# Elkapod_power_supply_controller_module.net
KiCad netlist of a schematic drawn in Altium Designer
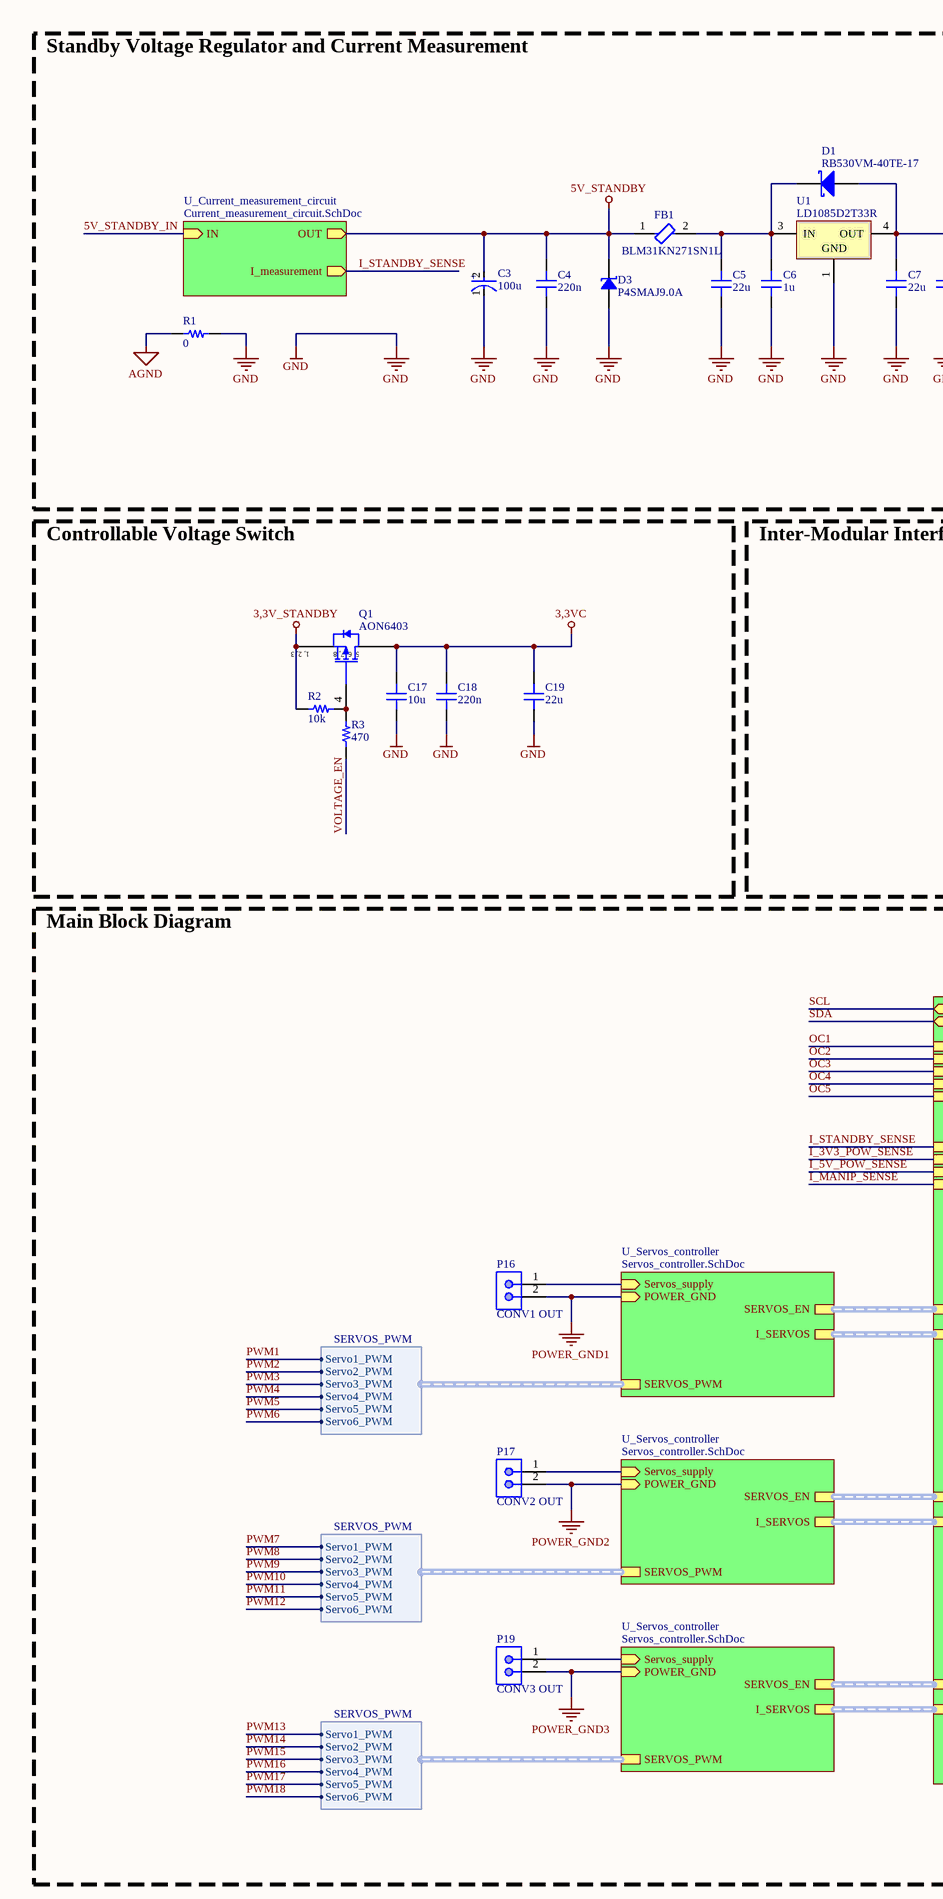
[diagram p0: Elkapod_power_supply_controller_module.SchDoc, left]
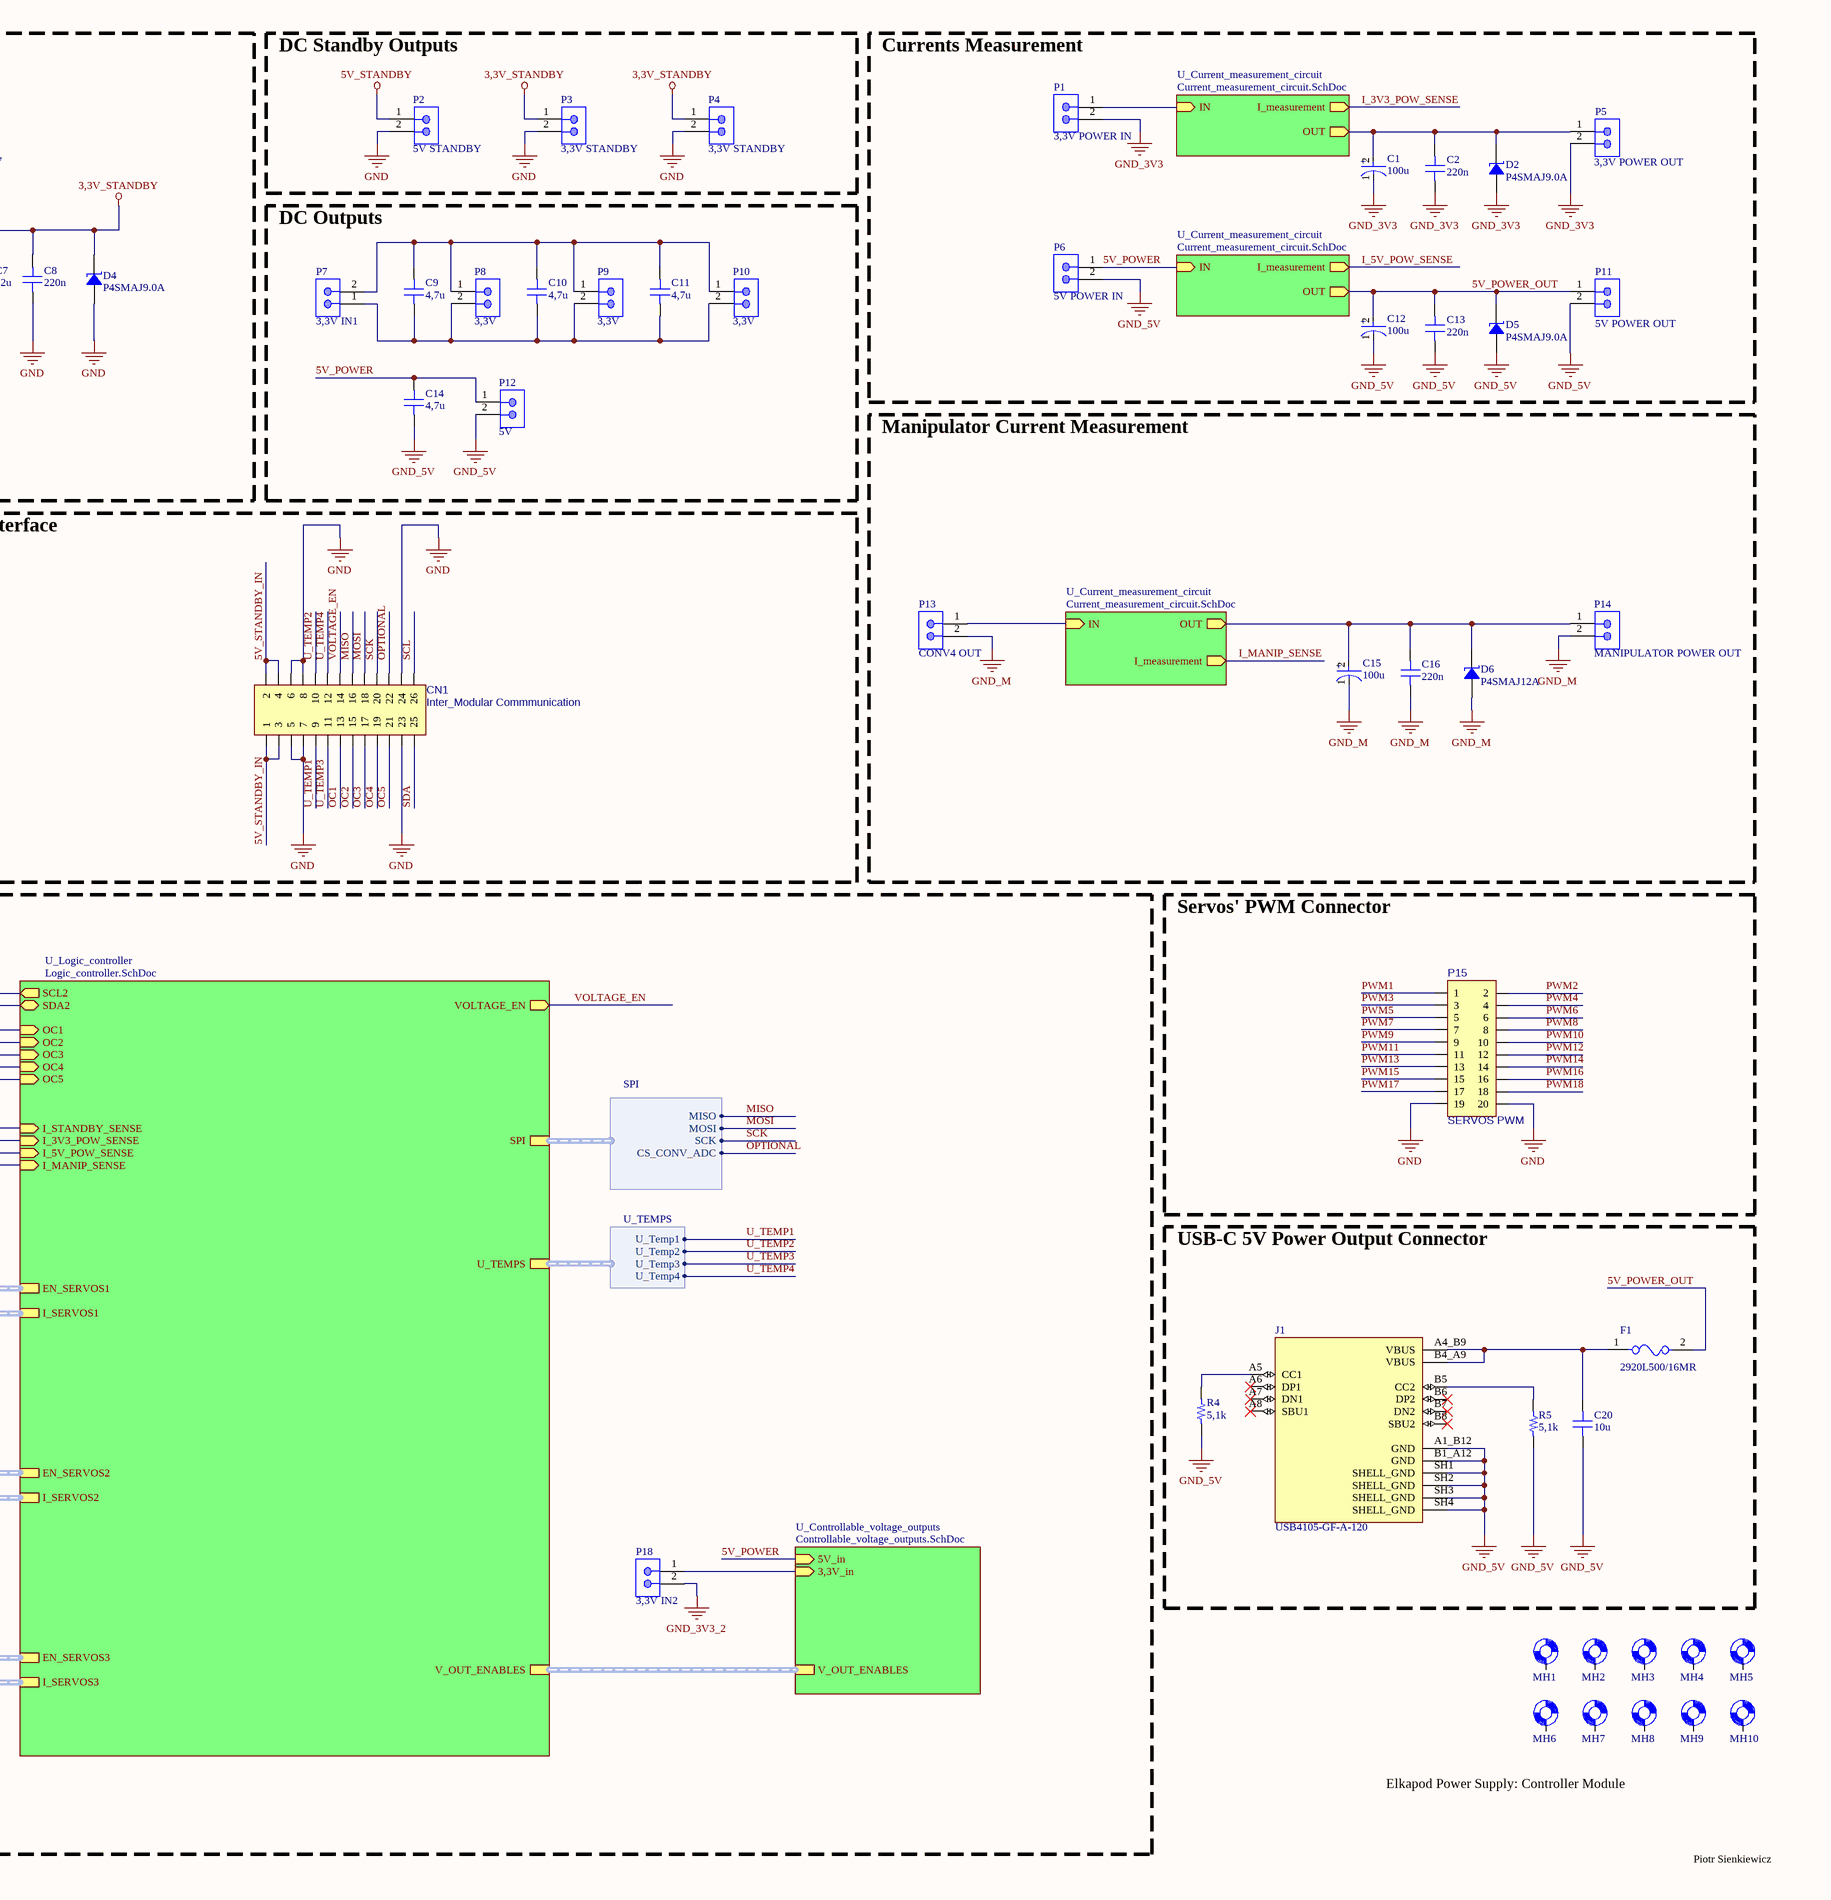
[diagram p1: Elkapod_power_supply_controller_module.SchDoc, right]

(export (version "E")
  (design (tool "Eeschema 10.0.6"))
  (components
    (comp (ref "C1")
      (value "100u")
      (footprint "FP-FKE-MFG")
      (description "CAP ALUM 100UF 20% 25V SMD")
      (fields (field (name "TOLERANCE") "20%") (field (name "VOLTAGE") "25V"))
      (libsource (lib "Altium Content Vault") (part "203bc49f2ac43e59fd269a8c329ed05"))
    )
    (comp (ref "C2")
      (value "220n")
      (footprint "CAP 0603_1608")
      (description "CAP CER 220nF 25V X5R 0603")
      (fields (field (name "PART NUMBER") "C0603C272F3GAC7867") (field (name "MANUFACTURER") "KEMET"))
      (libsource (lib "Celestial Altium Library - altium_library") (part "Capacitor"))
    )
    (comp (ref "C3")
      (value "100u")
      (footprint "FP-FKE-MFG")
      (description "CAP ALUM 100UF 20% 25V SMD")
      (fields (field (name "TOLERANCE") "20%") (field (name "VOLTAGE") "25V"))
      (libsource (lib "Altium Content Vault") (part "203bc49f2ac43e59fd269a8c329ed05"))
    )
    (comp (ref "C4")
      (value "220n")
      (footprint "CAP 0603_1608")
      (description "CAP CER 220nF 25V X5R 0603")
      (fields (field (name "PART NUMBER") "C0603C272F3GAC7867") (field (name "MANUFACTURER") "KEMET"))
      (libsource (lib "Celestial Altium Library - altium_library") (part "Capacitor"))
    )
    (comp (ref "C5")
      (value "22u")
      (footprint "CAP 0805_2012")
      (description "CAP CER 22UF 25V X7R 0805")
      (fields
        (field (name "PART NUMBER") "VJ0805Y684KXQTW1BC")
        (field (name "MANUFACTURER") "Vishay Vitramon")
      )
      (libsource (lib "Celestial Altium Library - altium_library") (part "Capacitor"))
    )
    (comp (ref "C6")
      (value "1u")
      (footprint "CAP 0603_1608")
      (description "CAP CER 1uF 16V X5R 0603")
      (fields (field (name "PART NUMBER") "C0603C272F3GAC7867") (field (name "MANUFACTURER") "KEMET"))
      (libsource (lib "Celestial Altium Library - altium_library") (part "Capacitor"))
    )
    (comp (ref "C7")
      (value "22u")
      (footprint "CAP 0805_2012")
      (description "CAP CER 22UF 25V X7R 0805")
      (fields
        (field (name "PART NUMBER") "VJ0805Y684KXQTW1BC")
        (field (name "MANUFACTURER") "Vishay Vitramon")
      )
      (libsource (lib "Celestial Altium Library - altium_library") (part "Capacitor"))
    )
    (comp (ref "C8")
      (value "220n")
      (footprint "CAP 0603_1608")
      (description "CAP CER 220nF 25V X5R 0603")
      (fields (field (name "PART NUMBER") "C0603C272F3GAC7867") (field (name "MANUFACTURER") "KEMET"))
      (libsource (lib "Celestial Altium Library - altium_library") (part "Capacitor"))
    )
    (comp (ref "C9")
      (value "4,7u")
      (footprint "CAP 0603_1608")
      (description "CAP CER 4,7uF 25V X5R 0603")
      (fields (field (name "PART NUMBER") "C0603C272F3GAC7867") (field (name "MANUFACTURER") "KEMET"))
      (libsource (lib "Celestial Altium Library - altium_library") (part "Capacitor"))
    )
    (comp (ref "C10")
      (value "4,7u")
      (footprint "CAP 0603_1608")
      (description "CAP CER 4,7uF 25V X5R 0603")
      (fields (field (name "PART NUMBER") "C0603C272F3GAC7867") (field (name "MANUFACTURER") "KEMET"))
      (libsource (lib "Celestial Altium Library - altium_library") (part "Capacitor"))
    )
    (comp (ref "C11")
      (value "4,7u")
      (footprint "CAP 0603_1608")
      (description "CAP CER 4,7uF 25V X5R 0603")
      (fields (field (name "PART NUMBER") "C0603C272F3GAC7867") (field (name "MANUFACTURER") "KEMET"))
      (libsource (lib "Celestial Altium Library - altium_library") (part "Capacitor"))
    )
    (comp (ref "C12")
      (value "100u")
      (footprint "FP-FKE-MFG")
      (description "CAP ALUM 100UF 20% 25V SMD")
      (fields (field (name "TOLERANCE") "20%") (field (name "VOLTAGE") "25V"))
      (libsource (lib "Altium Content Vault") (part "203bc49f2ac43e59fd269a8c329ed05"))
    )
    (comp (ref "C13")
      (value "220n")
      (footprint "CAP 0603_1608")
      (description "CAP CER 220nF 25V X5R 0603")
      (fields (field (name "PART NUMBER") "C0603C272F3GAC7867") (field (name "MANUFACTURER") "KEMET"))
      (libsource (lib "Celestial Altium Library - altium_library") (part "Capacitor"))
    )
    (comp (ref "C14")
      (value "4,7u")
      (footprint "CAP 0603_1608")
      (description "CAP CER 4,7uF 25V X5R 0603")
      (fields (field (name "PART NUMBER") "C0603C272F3GAC7867") (field (name "MANUFACTURER") "KEMET"))
      (libsource (lib "Celestial Altium Library - altium_library") (part "Capacitor"))
    )
    (comp (ref "C15")
      (value "100u")
      (footprint "FP-FKE-MFG")
      (description "CAP ALUM 100UF 20% 25V SMD")
      (fields (field (name "TOLERANCE") "20%") (field (name "VOLTAGE") "25V"))
      (libsource (lib "Altium Content Vault") (part "203bc49f2ac43e59fd269a8c329ed05"))
    )
    (comp (ref "C16")
      (value "220n")
      (footprint "CAP 0603_1608")
      (description "CAP CER 220nF 25V X5R 0603")
      (fields (field (name "PART NUMBER") "C0603C272F3GAC7867") (field (name "MANUFACTURER") "KEMET"))
      (libsource (lib "Celestial Altium Library - altium_library") (part "Capacitor"))
    )
    (comp (ref "C17")
      (value "10u")
      (footprint "CAP 0603_1608")
      (description "CAP CER 10uF 35V X5R 0603")
      (fields (field (name "PART NUMBER") "C0603C272F3GAC7867") (field (name "MANUFACTURER") "KEMET"))
      (libsource (lib "Celestial Altium Library - altium_library") (part "Capacitor"))
    )
    (comp (ref "C18")
      (value "220n")
      (footprint "CAP 0603_1608")
      (description "CAP CER 220nF 25V X5R 0603")
      (fields (field (name "PART NUMBER") "C0603C272F3GAC7867") (field (name "MANUFACTURER") "KEMET"))
      (libsource (lib "Celestial Altium Library - altium_library") (part "Capacitor"))
    )
    (comp (ref "C19")
      (value "22u")
      (footprint "CAP 0805_2012")
      (description "CAP CER 22UF 25V X7R 0805")
      (fields
        (field (name "PART NUMBER") "VJ0805Y684KXQTW1BC")
        (field (name "MANUFACTURER") "Vishay Vitramon")
      )
      (libsource (lib "Celestial Altium Library - altium_library") (part "Capacitor"))
    )
    (comp (ref "C20")
      (value "10u")
      (footprint "CAP 0603_1608")
      (description "CAP CER 10uF 35V X5R 0603")
      (fields (field (name "PART NUMBER") "C0603C272F3GAC7867") (field (name "MANUFACTURER") "KEMET"))
      (libsource (lib "Celestial Altium Library - altium_library") (part "Capacitor"))
    )
    (comp (ref "CN1")
      (value "Inter_Modular Commmunication")
      (footprint "GP_13x2")
      (libsource (lib "goldpin_male") (part "CN_13x2"))
    )
    (comp (ref "D1")
      (value "RB530VM-40TE-17")
      (footprint "SOD-323")
      (description "Schottky diode; 0,1A; 40V")
      (fields (field (name "PUBLISHER") "Altium Limited"))
      (libsource (lib "Infineon Discrete Diode") (part "BAS140W"))
    )
    (comp (ref "D2")
      (value "P4SMAJ9.0A")
      (footprint "DO214AC SMA")
      (description "TVS DIODE 9VDC DO214AC")
      (libsource (lib "Celestial Altium Library - altium_library") (part "DIODE TVS UNI"))
    )
    (comp (ref "D3")
      (value "P4SMAJ9.0A")
      (footprint "DO214AC SMA")
      (description "TVS DIODE 9VDC DO214AC")
      (libsource (lib "Celestial Altium Library - altium_library") (part "DIODE TVS UNI"))
    )
    (comp (ref "D4")
      (value "P4SMAJ9.0A")
      (footprint "DO214AC SMA")
      (description "TVS DIODE 9VDC DO214AC")
      (libsource (lib "Celestial Altium Library - altium_library") (part "DIODE TVS UNI"))
    )
    (comp (ref "D5")
      (value "P4SMAJ9.0A")
      (footprint "DO214AC SMA")
      (description "TVS DIODE 9VDC DO214AC")
      (libsource (lib "Celestial Altium Library - altium_library") (part "DIODE TVS UNI"))
    )
    (comp (ref "D6")
      (value "P4SMAJ12A")
      (footprint "DO214AC SMA")
      (description "TVS DIODE 12VDC DO214AC")
      (fields (field (name "PART NUMBER") "P4SMAJ9.0A"))
      (libsource (lib "Celestial Altium Library - altium_library") (part "DIODE TVS UNI"))
    )
    (comp (ref "F1")
      (value "2920L500/16MR")
      (footprint "FP-2920L-MFG")
      (description "PTC RESET FUSE 16V 5A 2920")
      (fields
        (field (name "MANUFACTURER") "Littelfuse")
        (field (name "OCTOPART") "https://octopart.com/2920l500%2F16mr-littelfuse-28867177")
      )
      (libsource (lib "Altium Content Vault") (part "5bcf9b9f640e542cf0359d10258e979"))
    )
    (comp (ref "FB1")
      (value "BLM31KN271SN1L")
      (footprint "FP-BLM31-0_2-t1_6-d3_3-MFG")
      (description "Chip Ferrite Bead, 1206, 270Ω @ 100MHz, 0.016Ω, 25%, 4.5A")
      (libsource (lib "Altium Content Vault") (part "5f30dd21d616792df468990f7003faa"))
    )
    (comp (ref "J1")
      (value "USB4105-GF-A-120")
      (footprint "USB4105-GF-A-120")
      (description "USB C socket; SMT; PIN: 16; top board mount; 5A")
      (libsource (lib "My_sockets") (part "USB4105-GF-A-120"))
    )
    (comp (ref "MH1")
      (value "M3 Mounting Hole")
      (footprint "M3_MOUNTING_HOLE")
      (libsource (lib "My_mounting_components") (part "M3 Mounting Hole"))
    )
    (comp (ref "MH2")
      (value "M3 Mounting Hole")
      (footprint "M3_MOUNTING_HOLE")
      (libsource (lib "My_mounting_components") (part "M3 Mounting Hole"))
    )
    (comp (ref "MH3")
      (value "M3 Mounting Hole")
      (footprint "M3_MOUNTING_HOLE")
      (libsource (lib "My_mounting_components") (part "M3 Mounting Hole"))
    )
    (comp (ref "MH4")
      (value "M3 Mounting Hole")
      (footprint "M3_MOUNTING_HOLE")
      (libsource (lib "My_mounting_components") (part "M3 Mounting Hole"))
    )
    (comp (ref "MH5")
      (value "M3 Mounting Hole")
      (footprint "M3_MOUNTING_HOLE")
      (libsource (lib "My_mounting_components") (part "M3 Mounting Hole"))
    )
    (comp (ref "MH6")
      (value "M3 Mounting Hole")
      (footprint "M3_MOUNTING_HOLE")
      (libsource (lib "My_mounting_components") (part "M3 Mounting Hole"))
    )
    (comp (ref "MH7")
      (value "M3 Mounting Hole")
      (footprint "M3_MOUNTING_HOLE")
      (libsource (lib "My_mounting_components") (part "M3 Mounting Hole"))
    )
    (comp (ref "MH8")
      (value "M3 Mounting Hole")
      (footprint "M3_MOUNTING_HOLE")
      (libsource (lib "My_mounting_components") (part "M3 Mounting Hole"))
    )
    (comp (ref "MH9")
      (value "M3 Mounting Hole")
      (footprint "M3_MOUNTING_HOLE")
      (libsource (lib "My_mounting_components") (part "M3 Mounting Hole"))
    )
    (comp (ref "MH10")
      (value "M3 Mounting Hole")
      (footprint "M3_MOUNTING_HOLE")
      (libsource (lib "My_mounting_components") (part "M3 Mounting Hole"))
    )
    (comp (ref "P1")
      (value "3,3V POWER IN")
      (footprint "2x2,5mm2_WIRE")
      (description "2x2,5mm2 wire pads")
      (libsource (lib "") (part "2X2,5mm2_WIRE_1"))
    )
    (comp (ref "P2")
      (value "5V STANDBY")
      (footprint "MOLX-22-23-2021_V")
      (fields (field (name "PARTNUMBER") "22-23-2021"))
      (libsource (lib "Altium Content Vault") (part "CN-1P-M-R2"))
    )
    (comp (ref "P3")
      (value "3,3V STANDBY")
      (footprint "MOLX-22-23-2021_V")
      (fields (field (name "PARTNUMBER") "22-23-2021"))
      (libsource (lib "Altium Content Vault") (part "CN-1P-M-R2"))
    )
    (comp (ref "P4")
      (value "3,3V STANDBY")
      (footprint "MOLX-22-23-2021_V")
      (fields (field (name "PARTNUMBER") "22-23-2021"))
      (libsource (lib "Altium Content Vault") (part "CN-1P-M-R2"))
    )
    (comp (ref "P5")
      (value "3,3V POWER OUT")
      (footprint "XT60PW-M")
      (description "XT60PW-M; 30A/500V angled female DC PCB socket (pin1 -> +, pin2 -> -)")
      (libsource (lib "My_sockets") (part "XT60PW-M"))
    )
    (comp (ref "P6")
      (value "5V POWER IN")
      (footprint "2x2,5mm2_WIRE")
      (description "2x2,5mm2 wire pads")
      (libsource (lib "") (part "2X2,5mm2_WIRE_1"))
    )
    (comp (ref "P7")
      (value "3,3V IN1")
      (footprint "2x2,5mm2_WIRE")
      (description "2x2,5mm2 wire pads")
      (libsource (lib "My_sockets") (part "2X2,5mm2_WIRE"))
    )
    (comp (ref "P8")
      (value "3,3V")
      (footprint "MOLX-22-23-2021_V")
      (fields (field (name "PARTNUMBER") "22-23-2021"))
      (libsource (lib "Altium Content Vault") (part "CN-1P-M-R2"))
    )
    (comp (ref "P9")
      (value "3,3V")
      (footprint "MOLX-22-23-2021_V")
      (fields (field (name "PARTNUMBER") "22-23-2021"))
      (libsource (lib "Altium Content Vault") (part "CN-1P-M-R2"))
    )
    (comp (ref "P10")
      (value "3,3V")
      (footprint "MOLX-22-23-2021_V")
      (fields (field (name "PARTNUMBER") "22-23-2021"))
      (libsource (lib "Altium Content Vault") (part "CN-1P-M-R2"))
    )
    (comp (ref "P11")
      (value "5V POWER OUT")
      (footprint "XT60PW-M")
      (description "XT60PW-M; 30A/500V angled female DC PCB socket (pin1 -> +, pin2 -> -)")
      (libsource (lib "My_sockets") (part "XT60PW-M"))
    )
    (comp (ref "P12")
      (value "5V")
      (footprint "MOLX-22-23-2021_V")
      (fields (field (name "PARTNUMBER") "22-23-2021"))
      (libsource (lib "Altium Content Vault") (part "CN-1P-M-R2"))
    )
    (comp (ref "P13")
      (value "CONV4 OUT")
      (footprint "2x2,5mm2_WIRE")
      (description "2x2,5mm2 wire pads")
      (libsource (lib "") (part "2X2,5mm2_WIRE_1"))
    )
    (comp (ref "P14")
      (value "MANIPULATOR POWER OUT")
      (footprint "XT60PW-M")
      (description "XT60PW-M; 30A/500V angled female DC PCB socket (pin1 -> +, pin2 -> -)")
      (libsource (lib "My_sockets") (part "XT60PW-M"))
    )
    (comp (ref "P15") (value "SERVOS PWM") (footprint "IDC20") (libsource (lib "idc") (part "CN_10x2")))
    (comp (ref "P16")
      (value "CONV1 OUT")
      (footprint "2x2,5mm2_WIRE")
      (description "2x2,5mm2 wire pads")
      (libsource (lib "") (part "2X2,5mm2_WIRE_1"))
    )
    (comp (ref "P17")
      (value "CONV2 OUT")
      (footprint "2x2,5mm2_WIRE")
      (description "2x2,5mm2 wire pads")
      (libsource (lib "") (part "2X2,5mm2_WIRE_1"))
    )
    (comp (ref "P18")
      (value "3,3V IN2")
      (footprint "2x2,5mm2_WIRE")
      (description "2x2,5mm2 wire pads")
      (libsource (lib "") (part "2X2,5mm2_WIRE_1"))
    )
    (comp (ref "P19")
      (value "CONV3 OUT")
      (footprint "2x2,5mm2_WIRE")
      (description "2x2,5mm2 wire pads")
      (libsource (lib "") (part "2X2,5mm2_WIRE_1"))
    )
    (comp (ref "Q1")
      (value "AON6403")
      (footprint "DFN5x6")
      (description "P-MOSFET; 67A; 30V; DFN5x6")
      (libsource (lib "My_transistors") (part "AON6403"))
    )
    (comp (ref "R1")
      (value "0")
      (footprint "RES 0603_1608")
      (description "RES 0 OHM 1% 0,1W 0603")
      (fields
        (field (name "PART NUMBER") "RNCS0603BKE10K0")
        (field (name "MANUFACTURER") "Stackpole Electronics Inc")
      )
      (libsource (lib "Celestial Altium Library - altium_library") (part "Resistor"))
    )
    (comp (ref "R2")
      (value "10k")
      (footprint "RES 0603_1608")
      (description "RES 10K OHM 1% 0,1W 0603")
      (fields
        (field (name "PART NUMBER") "RNCS0603BKE10K0")
        (field (name "MANUFACTURER") "Stackpole Electronics Inc")
      )
      (libsource (lib "Celestial Altium Library - altium_library") (part "Resistor"))
    )
    (comp (ref "R3")
      (value "470")
      (footprint "RES 0603_1608")
      (description "RES 470 OHM 1% 0,1W 0603")
      (fields
        (field (name "PART NUMBER") "RNCS0603BKE10K0")
        (field (name "MANUFACTURER") "Stackpole Electronics Inc")
      )
      (libsource (lib "Celestial Altium Library - altium_library") (part "Resistor"))
    )
    (comp (ref "R4")
      (value "5,1k")
      (footprint "RES 0603_1608")
      (description "RES 5,1K OHM 1% 0,1W 0603")
      (fields
        (field (name "PART NUMBER") "RNCS0603BKE10K0")
        (field (name "MANUFACTURER") "Stackpole Electronics Inc")
      )
      (libsource (lib "Celestial Altium Library - altium_library") (part "Resistor"))
    )
    (comp (ref "R5")
      (value "5,1k")
      (footprint "RES 0603_1608")
      (description "RES 5,1K OHM 1% 0,1W 0603")
      (fields
        (field (name "PART NUMBER") "RNCS0603BKE10K0")
        (field (name "MANUFACTURER") "Stackpole Electronics Inc")
      )
      (libsource (lib "Celestial Altium Library - altium_library") (part "Resistor"))
    )
    (comp (ref "U1")
      (value "LD1085D2T33R")
      (footprint "TO-263_M")
      (description "3A, Low Drop Positive Voltage Regulator, 3.3V, 3-Pin D2PAK")
      (libsource (lib "Altium Content Vault") (part "PM-REG-LD1085-SOT3"))
    )
  )
  (nets
    (net (code "4") (name "/3,3V_in") (class "Default")
      (node (ref "P18") (pin "1") (pinfunction "+_1") (pintype "passive"))
    )
    (net (code "5") (name "/5V_POWER") (class "Default")
      (node (ref "C14") (pin "2") (pinfunction "2_2") (pintype "passive"))
      (node (ref "P12") (pin "1") (pinfunction "1_1") (pintype "passive"))
      (node (ref "P6") (pin "1") (pinfunction "+_1") (pintype "passive"))
    )
    (net (code "6") (name "/5V_POWER_OUT") (class "Default")
      (node (ref "C12") (pin "2") (pinfunction "A_2") (pintype "passive"))
      (node (ref "C13") (pin "1") (pinfunction "1_1") (pintype "passive"))
      (node (ref "D5") (pin "2") (pinfunction "2_2") (pintype "passive"))
      (node (ref "F1") (pin "2") (pinfunction "2_2") (pintype "passive"))
      (node (ref "P11") (pin "1") (pinfunction "+_1") (pintype "passive"))
    )
    (net (code "7") (name "/5V_STANDBY_IN") (class "Default")
      (node (ref "CN1") (pin "1") (pinfunction "1_1") (pintype "passive"))
      (node (ref "CN1") (pin "2") (pinfunction "2_2") (pintype "passive"))
      (node (ref "CN1") (pin "3") (pinfunction "3_3") (pintype "passive"))
      (node (ref "CN1") (pin "4") (pinfunction "4_4") (pintype "passive"))
    )
    (net (code "11") (name "/IN") (class "Default")
      (node (ref "P1") (pin "1") (pinfunction "+_1") (pintype "passive"))
    )
    (net (code "12") (name "/IN_1") (class "Default")
      (node (ref "P13") (pin "1") (pinfunction "+_1") (pintype "passive"))
    )
    (net (code "20") (name "/MISO") (class "Default")
      (node (ref "CN1") (pin "16") (pinfunction "16_16") (pintype "passive"))
    )
    (net (code "21") (name "/MOSI") (class "Default")
      (node (ref "CN1") (pin "18") (pinfunction "18_18") (pintype "passive"))
    )
    (net (code "22") (name "/OC1") (class "Default")
      (node (ref "CN1") (pin "13") (pinfunction "13_13") (pintype "passive"))
    )
    (net (code "23") (name "/OC2") (class "Default")
      (node (ref "CN1") (pin "15") (pinfunction "15_15") (pintype "passive"))
    )
    (net (code "24") (name "/OC3") (class "Default")
      (node (ref "CN1") (pin "17") (pinfunction "17_17") (pintype "passive"))
    )
    (net (code "25") (name "/OC4") (class "Default")
      (node (ref "CN1") (pin "19") (pinfunction "19_19") (pintype "passive"))
    )
    (net (code "26") (name "/OC5") (class "Default")
      (node (ref "CN1") (pin "21") (pinfunction "21_21") (pintype "passive"))
    )
    (net (code "27") (name "/OPTIONAL") (class "Default")
      (node (ref "CN1") (pin "22") (pinfunction "22_22") (pintype "passive"))
    )
    (net (code "28") (name "/OUT") (class "Default")
      (node (ref "C1") (pin "2") (pinfunction "A_2") (pintype "passive"))
      (node (ref "C2") (pin "1") (pinfunction "1_1") (pintype "passive"))
      (node (ref "D2") (pin "2") (pinfunction "2_2") (pintype "passive"))
      (node (ref "P5") (pin "1") (pinfunction "+_1") (pintype "passive"))
    )
    (net (code "29") (name "/OUT_1") (class "Default")
      (node (ref "C15") (pin "2") (pinfunction "A_2") (pintype "passive"))
      (node (ref "C16") (pin "1") (pinfunction "1_1") (pintype "passive"))
      (node (ref "D6") (pin "2") (pinfunction "2_2") (pintype "passive"))
      (node (ref "P14") (pin "1") (pinfunction "+_1") (pintype "passive"))
    )
    (net (code "30") (name "/PWM1") (class "Default")
      (node (ref "P15") (pin "1") (pinfunction "1_1") (pintype "passive"))
    )
    (net (code "31") (name "/PWM2") (class "Default")
      (node (ref "P15") (pin "2") (pinfunction "2_2") (pintype "passive"))
    )
    (net (code "32") (name "/PWM3") (class "Default")
      (node (ref "P15") (pin "3") (pinfunction "3_3") (pintype "passive"))
    )
    (net (code "33") (name "/PWM4") (class "Default")
      (node (ref "P15") (pin "4") (pinfunction "4_4") (pintype "passive"))
    )
    (net (code "34") (name "/PWM5") (class "Default")
      (node (ref "P15") (pin "5") (pinfunction "5_5") (pintype "passive"))
    )
    (net (code "35") (name "/PWM6") (class "Default")
      (node (ref "P15") (pin "6") (pinfunction "6_6") (pintype "passive"))
    )
    (net (code "36") (name "/PWM7") (class "Default")
      (node (ref "P15") (pin "7") (pinfunction "7_7") (pintype "passive"))
    )
    (net (code "37") (name "/PWM8") (class "Default")
      (node (ref "P15") (pin "8") (pinfunction "8_8") (pintype "passive"))
    )
    (net (code "38") (name "/PWM9") (class "Default")
      (node (ref "P15") (pin "9") (pinfunction "9_9") (pintype "passive"))
    )
    (net (code "39") (name "/PWM10") (class "Default")
      (node (ref "P15") (pin "10") (pinfunction "10_10") (pintype "passive"))
    )
    (net (code "40") (name "/PWM11") (class "Default")
      (node (ref "P15") (pin "11") (pinfunction "11_11") (pintype "passive"))
    )
    (net (code "41") (name "/PWM12") (class "Default")
      (node (ref "P15") (pin "12") (pinfunction "12_12") (pintype "passive"))
    )
    (net (code "42") (name "/PWM13") (class "Default")
      (node (ref "P15") (pin "13") (pinfunction "13_13") (pintype "passive"))
    )
    (net (code "43") (name "/PWM14") (class "Default")
      (node (ref "P15") (pin "14") (pinfunction "14_14") (pintype "passive"))
    )
    (net (code "44") (name "/PWM15") (class "Default")
      (node (ref "P15") (pin "15") (pinfunction "15_15") (pintype "passive"))
    )
    (net (code "45") (name "/PWM16") (class "Default")
      (node (ref "P15") (pin "16") (pinfunction "16_16") (pintype "passive"))
    )
    (net (code "46") (name "/PWM17") (class "Default")
      (node (ref "P15") (pin "17") (pinfunction "17_17") (pintype "passive"))
    )
    (net (code "47") (name "/PWM18") (class "Default")
      (node (ref "P15") (pin "18") (pinfunction "18_18") (pintype "passive"))
    )
    (net (code "48") (name "/SCK") (class "Default")
      (node (ref "CN1") (pin "20") (pinfunction "20_20") (pintype "passive"))
    )
    (net (code "49") (name "/SCL") (class "Default")
      (node (ref "CN1") (pin "26") (pinfunction "26_26") (pintype "passive"))
    )
    (net (code "50") (name "/SDA") (class "Default")
      (node (ref "CN1") (pin "25") (pinfunction "25_25") (pintype "passive"))
    )
    (net (code "51") (name "/Servos_supply") (class "Default")
      (node (ref "P16") (pin "1") (pinfunction "+_1") (pintype "passive"))
    )
    (net (code "52") (name "/Servos_supply_1") (class "Default")
      (node (ref "P17") (pin "1") (pinfunction "+_1") (pintype "passive"))
    )
    (net (code "53") (name "/Servos_supply_2") (class "Default")
      (node (ref "P19") (pin "1") (pinfunction "+_1") (pintype "passive"))
    )
    (net (code "54") (name "/U_TEMP1") (class "Default")
      (node (ref "CN1") (pin "9") (pinfunction "9_9") (pintype "passive"))
    )
    (net (code "55") (name "/U_TEMP2") (class "Default")
      (node (ref "CN1") (pin "10") (pinfunction "10_10") (pintype "passive"))
    )
    (net (code "56") (name "/U_TEMP3") (class "Default")
      (node (ref "CN1") (pin "11") (pinfunction "11_11") (pintype "passive"))
    )
    (net (code "57") (name "/U_TEMP4") (class "Default")
      (node (ref "CN1") (pin "12") (pinfunction "12_12") (pintype "passive"))
    )
    (net (code "58") (name "/VOLTAGE_EN") (class "Default")
      (node (ref "CN1") (pin "14") (pinfunction "14_14") (pintype "passive"))
      (node (ref "R3") (pin "2") (pinfunction "2_2") (pintype "passive"))
    )
    (net (code "63") (name "3,3VC") (class "Default")
      (node (ref "C17") (pin "2") (pinfunction "2_2") (pintype "passive"))
      (node (ref "C18") (pin "2") (pinfunction "2_2") (pintype "passive"))
      (node (ref "C19") (pin "2") (pinfunction "2_2") (pintype "passive"))
      (node (ref "Q1") (pin "5") (pinfunction "D_5") (pintype "passive"))
    )
    (net (code "64") (name "3,3V_STANDBY") (class "Default")
      (node (ref "C7") (pin "2") (pinfunction "2_2") (pintype "passive"))
      (node (ref "C8") (pin "2") (pinfunction "2_2") (pintype "passive"))
      (node (ref "D1") (pin "2") (pinfunction "A_2") (pintype "passive"))
      (node (ref "D4") (pin "2") (pinfunction "2_2") (pintype "passive"))
      (node (ref "P3") (pin "1") (pinfunction "1_1") (pintype "passive"))
      (node (ref "P4") (pin "1") (pinfunction "1_1") (pintype "passive"))
      (node (ref "Q1") (pin "1") (pinfunction "S_1") (pintype "passive"))
      (node (ref "Q1") (pin "2") (pinfunction "S_2") (pintype "passive"))
      (node (ref "Q1") (pin "3") (pinfunction "S_3") (pintype "passive"))
      (node (ref "R2") (pin "1") (pinfunction "1_1") (pintype "passive"))
      (node (ref "U1") (pin "4") (pinfunction "OUT_4") (pintype "power_in"))
    )
    (net (code "65") (name "5V_STANDBY") (class "Default")
      (node (ref "C3") (pin "2") (pinfunction "A_2") (pintype "passive"))
      (node (ref "C4") (pin "1") (pinfunction "1_1") (pintype "passive"))
      (node (ref "D3") (pin "2") (pinfunction "2_2") (pintype "passive"))
      (node (ref "FB1") (pin "1") (pinfunction "1_1") (pintype "passive"))
      (node (ref "P2") (pin "1") (pinfunction "1_1") (pintype "passive"))
    )
    (net (code "66") (name "AGND") (class "Default")
      (node (ref "R1") (pin "1") (pinfunction "1_1") (pintype "passive"))
    )
    (net (code "67") (name "GND") (class "Default")
      (node (ref "C17") (pin "1") (pinfunction "1_1") (pintype "passive"))
      (node (ref "C18") (pin "1") (pinfunction "1_1") (pintype "passive"))
      (node (ref "C19") (pin "1") (pinfunction "1_1") (pintype "passive"))
      (node (ref "C3") (pin "1") (pinfunction "C_1") (pintype "passive"))
      (node (ref "C4") (pin "2") (pinfunction "2_2") (pintype "passive"))
      (node (ref "C5") (pin "1") (pinfunction "1_1") (pintype "passive"))
      (node (ref "C6") (pin "1") (pinfunction "1_1") (pintype "passive"))
      (node (ref "C7") (pin "1") (pinfunction "1_1") (pintype "passive"))
      (node (ref "C8") (pin "1") (pinfunction "1_1") (pintype "passive"))
      (node (ref "CN1") (pin "23") (pinfunction "23_23") (pintype "passive"))
      (node (ref "CN1") (pin "24") (pinfunction "24_24") (pintype "passive"))
      (node (ref "CN1") (pin "5") (pinfunction "5_5") (pintype "passive"))
      (node (ref "CN1") (pin "6") (pinfunction "6_6") (pintype "passive"))
      (node (ref "CN1") (pin "7") (pinfunction "7_7") (pintype "passive"))
      (node (ref "CN1") (pin "8") (pinfunction "8_8") (pintype "passive"))
      (node (ref "D3") (pin "1") (pinfunction "1_1") (pintype "passive"))
      (node (ref "D4") (pin "1") (pinfunction "1_1") (pintype "passive"))
      (node (ref "P15") (pin "19") (pinfunction "19_19") (pintype "passive"))
      (node (ref "P15") (pin "20") (pinfunction "20_20") (pintype "passive"))
      (node (ref "P2") (pin "2") (pinfunction "2_2") (pintype "passive"))
      (node (ref "P3") (pin "2") (pinfunction "2_2") (pintype "passive"))
      (node (ref "P4") (pin "2") (pinfunction "2_2") (pintype "passive"))
      (node (ref "R1") (pin "2") (pinfunction "2_2") (pintype "passive"))
      (node (ref "U1") (pin "1") (pinfunction "GND_1") (pintype "power_in"))
    )
    (net (code "68") (name "GND_3V3") (class "Default")
      (node (ref "C1") (pin "1") (pinfunction "C_1") (pintype "passive"))
      (node (ref "C2") (pin "2") (pinfunction "2_2") (pintype "passive"))
      (node (ref "D2") (pin "1") (pinfunction "1_1") (pintype "passive"))
      (node (ref "P1") (pin "2") (pinfunction "-_2") (pintype "passive"))
      (node (ref "P5") (pin "2") (pinfunction "-_2") (pintype "passive"))
    )
    (net (code "69") (name "GND_3V3_2") (class "Default")
      (node (ref "P18") (pin "2") (pinfunction "-_2") (pintype "passive"))
    )
    (net (code "70") (name "GND_5V") (class "Default")
      (node (ref "C12") (pin "1") (pinfunction "C_1") (pintype "passive"))
      (node (ref "C13") (pin "2") (pinfunction "2_2") (pintype "passive"))
      (node (ref "C14") (pin "1") (pinfunction "1_1") (pintype "passive"))
      (node (ref "C20") (pin "1") (pinfunction "1_1") (pintype "passive"))
      (node (ref "D5") (pin "1") (pinfunction "1_1") (pintype "passive"))
      (node (ref "J1") (pin "A1_B12") (pinfunction "GND_A1_B12") (pintype "power_in"))
      (node (ref "J1") (pin "B1_A12") (pinfunction "GND_B1_A12") (pintype "power_in"))
      (node (ref "J1") (pin "SH1") (pinfunction "SHELL_GND_SH1") (pintype "power_in"))
      (node (ref "J1") (pin "SH2") (pinfunction "SHELL_GND_SH2") (pintype "power_in"))
      (node (ref "J1") (pin "SH3") (pinfunction "SHELL_GND_SH3") (pintype "power_in"))
      (node (ref "J1") (pin "SH4") (pinfunction "SHELL_GND_SH4") (pintype "power_in"))
      (node (ref "P11") (pin "2") (pinfunction "-_2") (pintype "passive"))
      (node (ref "P12") (pin "2") (pinfunction "2_2") (pintype "passive"))
      (node (ref "P6") (pin "2") (pinfunction "-_2") (pintype "passive"))
      (node (ref "R4") (pin "2") (pinfunction "2_2") (pintype "passive"))
      (node (ref "R5") (pin "2") (pinfunction "2_2") (pintype "passive"))
    )
    (net (code "71") (name "GND_M") (class "Default")
      (node (ref "C15") (pin "1") (pinfunction "C_1") (pintype "passive"))
      (node (ref "C16") (pin "2") (pinfunction "2_2") (pintype "passive"))
      (node (ref "D6") (pin "1") (pinfunction "1_1") (pintype "passive"))
      (node (ref "P13") (pin "2") (pinfunction "-_2") (pintype "passive"))
      (node (ref "P14") (pin "2") (pinfunction "-_2") (pintype "passive"))
    )
    (net (code "72") (name "Net-(C20-Pad2)") (class "Default")
      (node (ref "C20") (pin "2") (pinfunction "2_2") (pintype "passive"))
      (node (ref "F1") (pin "1") (pinfunction "1_1") (pintype "passive"))
      (node (ref "J1") (pin "A4_B9") (pinfunction "VBUS_A4_B9") (pintype "power_in"))
      (node (ref "J1") (pin "B4_A9") (pinfunction "VBUS_B4_A9") (pintype "power_in"))
    )
    (net (code "73") (name "Net-(D1-K)") (class "Default")
      (node (ref "C5") (pin "2") (pinfunction "2_2") (pintype "passive"))
      (node (ref "C6") (pin "2") (pinfunction "2_2") (pintype "passive"))
      (node (ref "D1") (pin "1") (pinfunction "K_1") (pintype "passive"))
      (node (ref "FB1") (pin "2") (pinfunction "2_2") (pintype "passive"))
      (node (ref "U1") (pin "3") (pinfunction "IN_3") (pintype "power_in"))
    )
    (net (code "74") (name "Net-(J1-CC1)") (class "Default")
      (node (ref "J1") (pin "A5") (pinfunction "CC1_A5") (pintype "bidirectional"))
      (node (ref "R4") (pin "1") (pinfunction "1_1") (pintype "passive"))
    )
    (net (code "75") (name "Net-(J1-CC2)") (class "Default")
      (node (ref "J1") (pin "B5") (pinfunction "CC2_B5") (pintype "bidirectional"))
      (node (ref "R5") (pin "1") (pinfunction "1_1") (pintype "passive"))
    )
    (net (code "76") (name "Net-(P7-+)") (class "Default")
      (node (ref "C10") (pin "1") (pinfunction "1_1") (pintype "passive"))
      (node (ref "C11") (pin "1") (pinfunction "1_1") (pintype "passive"))
      (node (ref "C9") (pin "1") (pinfunction "1_1") (pintype "passive"))
      (node (ref "P10") (pin "2") (pinfunction "2_2") (pintype "passive"))
      (node (ref "P7") (pin "1") (pinfunction "+_1") (pintype "passive"))
      (node (ref "P8") (pin "2") (pinfunction "2_2") (pintype "passive"))
      (node (ref "P9") (pin "2") (pinfunction "2_2") (pintype "passive"))
    )
    (net (code "77") (name "Net-(P7--)") (class "Default")
      (node (ref "C10") (pin "2") (pinfunction "2_2") (pintype "passive"))
      (node (ref "C11") (pin "2") (pinfunction "2_2") (pintype "passive"))
      (node (ref "C9") (pin "2") (pinfunction "2_2") (pintype "passive"))
      (node (ref "P10") (pin "1") (pinfunction "1_1") (pintype "passive"))
      (node (ref "P7") (pin "2") (pinfunction "-_2") (pintype "passive"))
      (node (ref "P8") (pin "1") (pinfunction "1_1") (pintype "passive"))
      (node (ref "P9") (pin "1") (pinfunction "1_1") (pintype "passive"))
    )
    (net (code "78") (name "Net-(Q1-G)") (class "Default")
      (node (ref "Q1") (pin "4") (pinfunction "G_4") (pintype "passive"))
      (node (ref "R2") (pin "2") (pinfunction "2_2") (pintype "passive"))
      (node (ref "R3") (pin "1") (pinfunction "1_1") (pintype "passive"))
    )
    (net (code "79") (name "POWER_GND1") (class "Default")
      (node (ref "P16") (pin "2") (pinfunction "-_2") (pintype "passive"))
    )
    (net (code "80") (name "POWER_GND2") (class "Default")
      (node (ref "P17") (pin "2") (pinfunction "-_2") (pintype "passive"))
    )
    (net (code "81") (name "POWER_GND3") (class "Default")
      (node (ref "P19") (pin "2") (pinfunction "-_2") (pintype "passive"))
    )
    (net (code "82") (name "unconnected-(J1-DN1-PadA7)") (class "Default")
      (node (ref "J1") (pin "A7") (pinfunction "DN1_A7") (pintype "bidirectional+no_connect"))
    )
    (net (code "83") (name "unconnected-(J1-DN2-PadB7)") (class "Default")
      (node (ref "J1") (pin "B7") (pinfunction "DN2_B7") (pintype "bidirectional+no_connect"))
    )
    (net (code "84") (name "unconnected-(J1-DP1-PadA6)") (class "Default")
      (node (ref "J1") (pin "A6") (pinfunction "DP1_A6") (pintype "bidirectional+no_connect"))
    )
    (net (code "85") (name "unconnected-(J1-DP2-PadB6)") (class "Default")
      (node (ref "J1") (pin "B6") (pinfunction "DP2_B6") (pintype "bidirectional+no_connect"))
    )
    (net (code "86") (name "unconnected-(J1-SBU1-PadA8)") (class "Default")
      (node (ref "J1") (pin "A8") (pinfunction "SBU1_A8") (pintype "bidirectional+no_connect"))
    )
    (net (code "87") (name "unconnected-(J1-SBU2-PadB8)") (class "Default")
      (node (ref "J1") (pin "B8") (pinfunction "SBU2_B8") (pintype "bidirectional+no_connect"))
    )
    (net (code "88") (name "unconnected-(MH1-Pad1)") (class "Default")
      (node (ref "MH1") (pin "1") (pinfunction "1_1") (pintype "passive"))
    )
    (net (code "89") (name "unconnected-(MH2-Pad1)") (class "Default")
      (node (ref "MH2") (pin "1") (pinfunction "1_1") (pintype "passive"))
    )
    (net (code "90") (name "unconnected-(MH3-Pad1)") (class "Default")
      (node (ref "MH3") (pin "1") (pinfunction "1_1") (pintype "passive"))
    )
    (net (code "91") (name "unconnected-(MH4-Pad1)") (class "Default")
      (node (ref "MH4") (pin "1") (pinfunction "1_1") (pintype "passive"))
    )
    (net (code "92") (name "unconnected-(MH5-Pad1)") (class "Default")
      (node (ref "MH5") (pin "1") (pinfunction "1_1") (pintype "passive"))
    )
    (net (code "93") (name "unconnected-(MH6-Pad1)") (class "Default")
      (node (ref "MH6") (pin "1") (pinfunction "1_1") (pintype "passive"))
    )
    (net (code "94") (name "unconnected-(MH7-Pad1)") (class "Default")
      (node (ref "MH7") (pin "1") (pinfunction "1_1") (pintype "passive"))
    )
    (net (code "95") (name "unconnected-(MH8-Pad1)") (class "Default")
      (node (ref "MH8") (pin "1") (pinfunction "1_1") (pintype "passive"))
    )
    (net (code "96") (name "unconnected-(MH9-Pad1)") (class "Default")
      (node (ref "MH9") (pin "1") (pinfunction "1_1") (pintype "passive"))
    )
    (net (code "97") (name "unconnected-(MH10-Pad1)") (class "Default")
      (node (ref "MH10") (pin "1") (pinfunction "1_1") (pintype "passive"))
    )
  )
)
